# Gadget-Box-PiZero.net
KiCad netlist of a schematic drawn in EAGLE
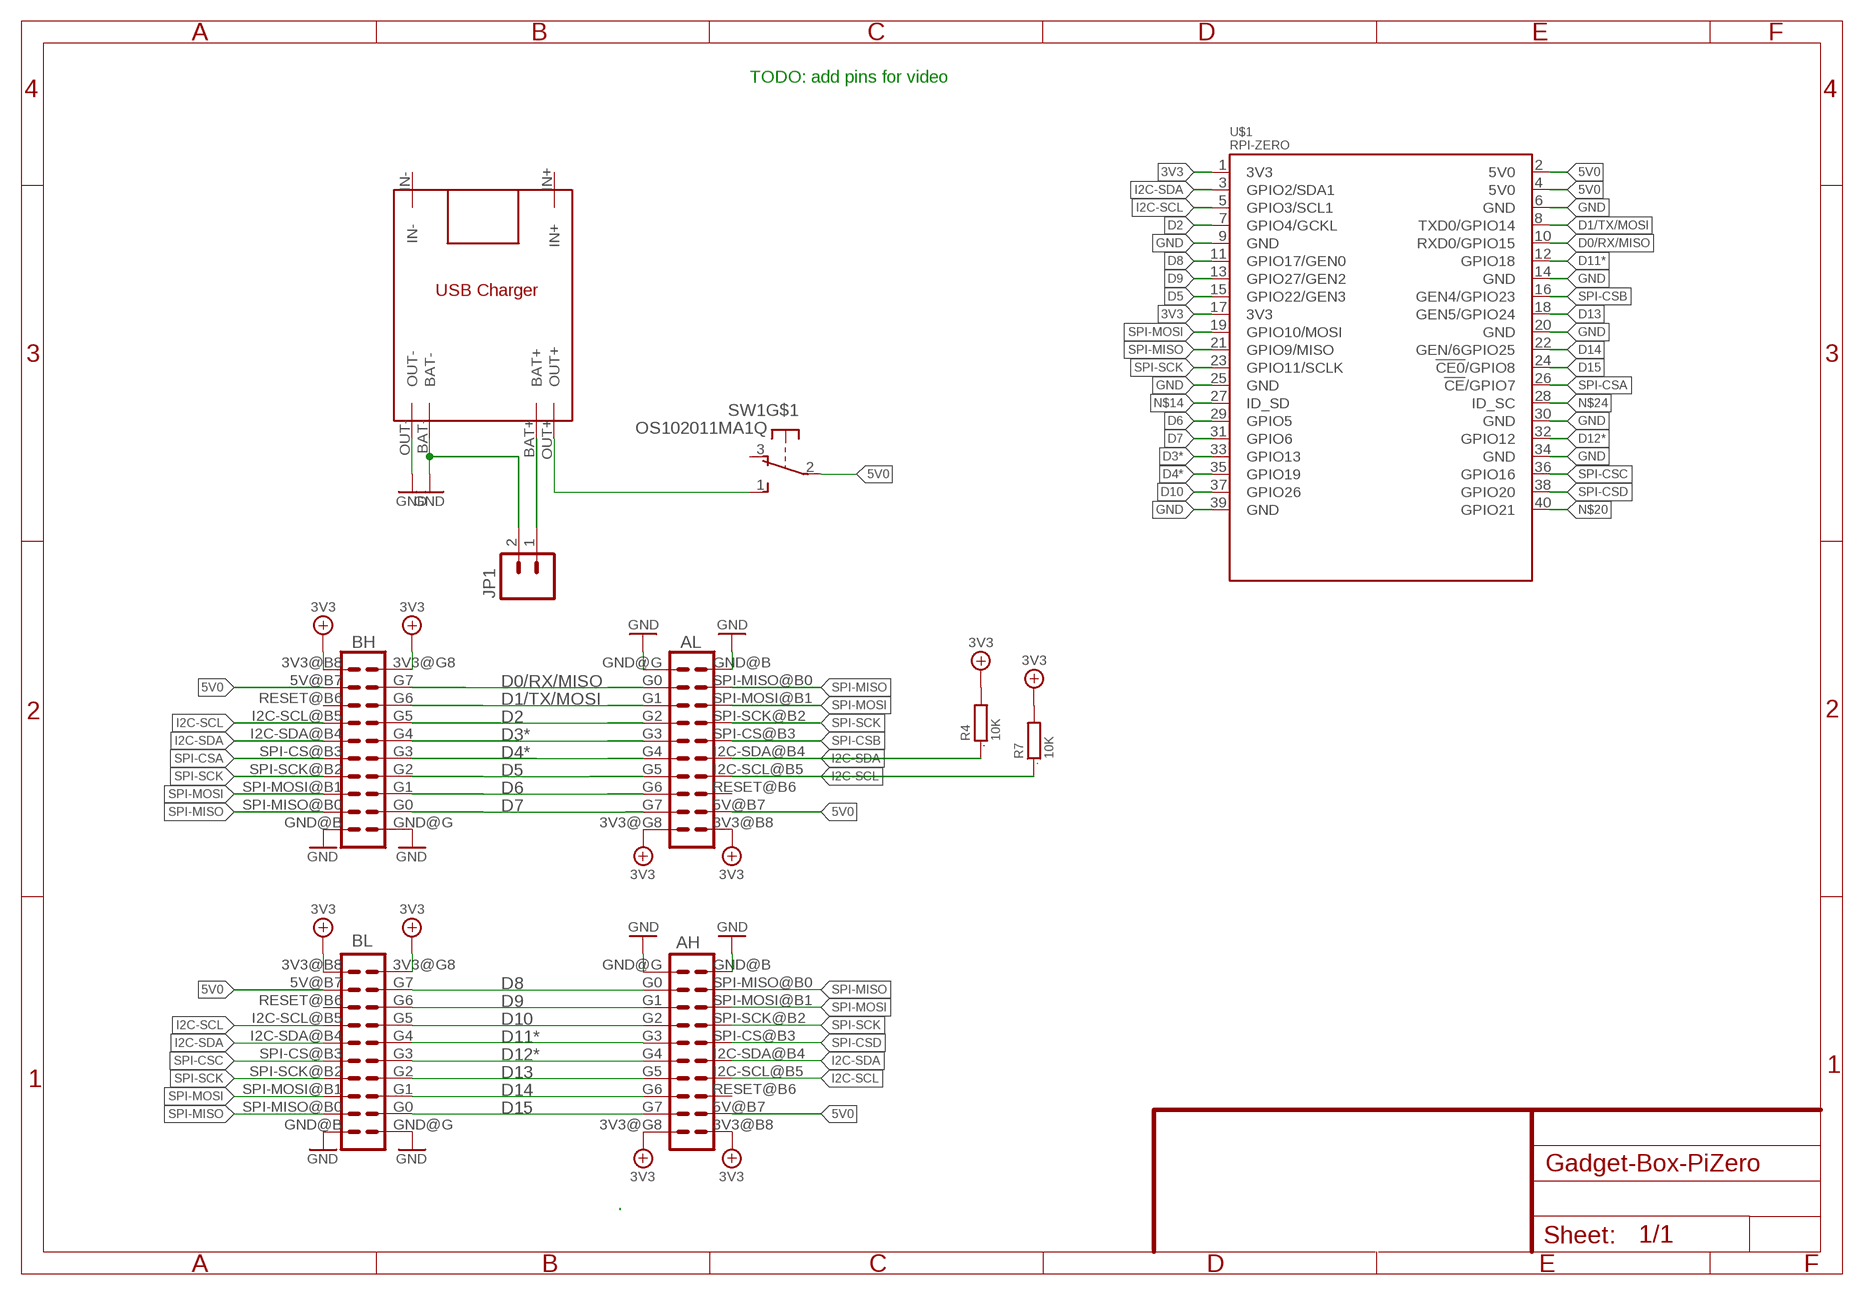
[diagram p0: schematic, sheet 1]

(export (version "E")
  (design (tool "Eeschema 10.0.6"))
  (components
    (comp (ref "AH")
      (value "ECOGECOG_SLOT_ALT1")
      (footprint "eagle-import:ECOG_ALT1")
      (libsource (lib "eagle-import") (part "ECOGECOG_SLOT_ALT1"))
    )
    (comp (ref "AL")
      (value "ECOGECOG_SLOT_ALT1")
      (footprint "eagle-import:ECOG_ALT1")
      (libsource (lib "eagle-import") (part "ECOGECOG_SLOT_ALT1"))
    )
    (comp (ref "BH")
      (value "ECOGECOG_SLOT_ALT1")
      (footprint "eagle-import:ECOG_ALT1")
      (libsource (lib "eagle-import") (part "ECOGECOG_SLOT_ALT1"))
    )
    (comp (ref "BL")
      (value "ECOGECOG_SLOT_ALT1")
      (footprint "eagle-import:ECOG_ALT1")
      (libsource (lib "eagle-import") (part "ECOGECOG_SLOT_ALT1"))
    )
    (comp (ref "JP1")
      (value "M02-JST-2-PTH-NO_SILK")
      (footprint "eagle-import:JST-2-PTH-NS")
      (libsource (lib "eagle-import") (part "M02-JST-2-PTH-NO_SILK"))
    )
    (comp (ref "R4")
      (value "10K")
      (footprint "eagle-import:0603")
      (fields
        (field (name "PARTNO") "RC0603JR-0710KL,YAGEO (VA),dk,311-10KGRCT-ND,RES SMD 10K OHM 5% 1/10W 0603 , REF36")
      )
      (libsource (lib "eagle-import") (part "R0603"))
    )
    (comp (ref "R7")
      (value "10K")
      (footprint "eagle-import:0603")
      (fields
        (field (name "PARTNO") "RC0603JR-0710KL,YAGEO (VA),dk,311-10KGRCT-ND,RES SMD 10K OHM 5% 1/10W 0603 , REF36")
      )
      (libsource (lib "eagle-import") (part "R0603"))
    )
    (comp (ref "SW1")
      (value "OS102011MA1Q")
      (footprint "eagle-import:OS102011MA1Q")
      (libsource (lib "eagle-import") (part "OS102011MA1Q"))
    )
    (comp (ref "U$1")
      (value "RPI-ZERO")
      (footprint "eagle-import:RASPBERRYPI_BASTELSTUBE_V13_RASPI_BOARD_B+_FULL")
      (libsource (lib "eagle-import") (part "RPI-ZERO"))
    )
    (comp (ref "U$2")
      (value "TP4056")
      (footprint "eagle-import:TP4056")
      (libsource (lib "eagle-import") (part "TP4056"))
    )
  )
  (nets
    (net (code "1") (name "3V3") (class "Default")
      (node (ref "AH") (pin "3V3@B8") (pinfunction "3V3_3V3@B8") (pintype "passive"))
      (node (ref "AH") (pin "3V3@G8") (pinfunction "3V3_3V3@G8") (pintype "passive"))
      (node (ref "AL") (pin "3V3@B8") (pinfunction "3V3_3V3@B8") (pintype "passive"))
      (node (ref "AL") (pin "3V3@G8") (pinfunction "3V3_3V3@G8") (pintype "passive"))
      (node (ref "BH") (pin "3V3@B8") (pinfunction "3V3_3V3@B8") (pintype "passive"))
      (node (ref "BH") (pin "3V3@G8") (pinfunction "3V3_3V3@G8") (pintype "passive"))
      (node (ref "BL") (pin "3V3@B8") (pinfunction "3V3_3V3@B8") (pintype "passive"))
      (node (ref "BL") (pin "3V3@G8") (pinfunction "3V3_3V3@G8") (pintype "passive"))
      (node (ref "R4") (pin "2") (pinfunction "2_2") (pintype "passive"))
      (node (ref "R7") (pin "2") (pinfunction "2_2") (pintype "passive"))
      (node (ref "U$1") (pin "1") (pinfunction "3V3_1") (pintype "power_in"))
      (node (ref "U$1") (pin "17") (pinfunction "3V3_17") (pintype "power_in"))
    )
    (net (code "2") (name "5V0") (class "Default")
      (node (ref "AH") (pin "5V@B7") (pinfunction "5V_5V@B7") (pintype "passive"))
      (node (ref "AL") (pin "5V@B7") (pinfunction "5V_5V@B7") (pintype "passive"))
      (node (ref "BH") (pin "5V@B7") (pinfunction "5V_5V@B7") (pintype "passive"))
      (node (ref "BL") (pin "5V@B7") (pinfunction "5V_5V@B7") (pintype "passive"))
      (node (ref "SW1") (pin "2") (pinfunction "P_2") (pintype "passive"))
      (node (ref "U$1") (pin "2") (pinfunction "5V0_2") (pintype "power_in"))
      (node (ref "U$1") (pin "4") (pinfunction "5V0_4") (pintype "power_in"))
    )
    (net (code "3") (name "D0{slash}RX{slash}MISO") (class "Default")
      (node (ref "AL") (pin "G0") (pinfunction "G0_G0") (pintype "passive"))
      (node (ref "BH") (pin "G7") (pinfunction "G7_G7") (pintype "passive"))
      (node (ref "U$1") (pin "10") (pinfunction "RXD0/GPIO15_10") (pintype "bidirectional"))
    )
    (net (code "4") (name "D1{slash}TX{slash}MOSI") (class "Default")
      (node (ref "AL") (pin "G1") (pinfunction "G1_G1") (pintype "passive"))
      (node (ref "BH") (pin "G6") (pinfunction "G6_G6") (pintype "passive"))
      (node (ref "U$1") (pin "8") (pinfunction "TXD0/GPIO14_8") (pintype "bidirectional"))
    )
    (net (code "5") (name "D2") (class "Default")
      (node (ref "AL") (pin "G2") (pinfunction "G2_G2") (pintype "passive"))
      (node (ref "BH") (pin "G5") (pinfunction "G5_G5") (pintype "passive"))
      (node (ref "U$1") (pin "7") (pinfunction "GPIO4/GCKL_7") (pintype "bidirectional"))
    )
    (net (code "6") (name "D3*") (class "Default")
      (node (ref "AL") (pin "G3") (pinfunction "G3_G3") (pintype "passive"))
      (node (ref "BH") (pin "G4") (pinfunction "G4_G4") (pintype "passive"))
      (node (ref "U$1") (pin "33") (pinfunction "GPIO13_33") (pintype "bidirectional"))
    )
    (net (code "7") (name "D4*") (class "Default")
      (node (ref "AL") (pin "G4") (pinfunction "G4_G4") (pintype "passive"))
      (node (ref "BH") (pin "G3") (pinfunction "G3_G3") (pintype "passive"))
      (node (ref "U$1") (pin "35") (pinfunction "GPIO19_35") (pintype "bidirectional"))
    )
    (net (code "8") (name "D5") (class "Default")
      (node (ref "AL") (pin "G5") (pinfunction "G5_G5") (pintype "passive"))
      (node (ref "BH") (pin "G2") (pinfunction "G2_G2") (pintype "passive"))
      (node (ref "U$1") (pin "15") (pinfunction "GPIO22/GEN3_15") (pintype "bidirectional"))
    )
    (net (code "9") (name "D6") (class "Default")
      (node (ref "AL") (pin "G6") (pinfunction "G6_G6") (pintype "passive"))
      (node (ref "BH") (pin "G1") (pinfunction "G1_G1") (pintype "passive"))
      (node (ref "U$1") (pin "29") (pinfunction "GPIO5_29") (pintype "bidirectional"))
    )
    (net (code "10") (name "D7") (class "Default")
      (node (ref "AL") (pin "G7") (pinfunction "G7_G7") (pintype "passive"))
      (node (ref "BH") (pin "G0") (pinfunction "G0_G0") (pintype "passive"))
      (node (ref "U$1") (pin "31") (pinfunction "GPIO6_31") (pintype "bidirectional"))
    )
    (net (code "11") (name "D8") (class "Default")
      (node (ref "AH") (pin "G0") (pinfunction "G0_G0") (pintype "passive"))
      (node (ref "BL") (pin "G7") (pinfunction "G7_G7") (pintype "passive"))
      (node (ref "U$1") (pin "11") (pinfunction "GPIO17/GEN0_11") (pintype "bidirectional"))
    )
    (net (code "12") (name "D9") (class "Default")
      (node (ref "AH") (pin "G1") (pinfunction "G1_G1") (pintype "passive"))
      (node (ref "BL") (pin "G6") (pinfunction "G6_G6") (pintype "passive"))
      (node (ref "U$1") (pin "13") (pinfunction "GPIO27/GEN2_13") (pintype "bidirectional"))
    )
    (net (code "13") (name "D10") (class "Default")
      (node (ref "AH") (pin "G2") (pinfunction "G2_G2") (pintype "passive"))
      (node (ref "BL") (pin "G5") (pinfunction "G5_G5") (pintype "passive"))
      (node (ref "U$1") (pin "37") (pinfunction "GPIO26_37") (pintype "bidirectional"))
    )
    (net (code "14") (name "D11*") (class "Default")
      (node (ref "AH") (pin "G3") (pinfunction "G3_G3") (pintype "passive"))
      (node (ref "BL") (pin "G4") (pinfunction "G4_G4") (pintype "passive"))
      (node (ref "U$1") (pin "12") (pinfunction "GPIO18_12") (pintype "bidirectional"))
    )
    (net (code "15") (name "D12*") (class "Default")
      (node (ref "AH") (pin "G4") (pinfunction "G4_G4") (pintype "passive"))
      (node (ref "BL") (pin "G3") (pinfunction "G3_G3") (pintype "passive"))
      (node (ref "U$1") (pin "32") (pinfunction "GPIO12_32") (pintype "bidirectional"))
    )
    (net (code "16") (name "D13") (class "Default")
      (node (ref "AH") (pin "G5") (pinfunction "G5_G5") (pintype "passive"))
      (node (ref "BL") (pin "G2") (pinfunction "G2_G2") (pintype "passive"))
      (node (ref "U$1") (pin "18") (pinfunction "GEN5/GPIO24_18") (pintype "bidirectional"))
    )
    (net (code "17") (name "D14") (class "Default")
      (node (ref "AH") (pin "G6") (pinfunction "G6_G6") (pintype "passive"))
      (node (ref "BL") (pin "G1") (pinfunction "G1_G1") (pintype "passive"))
      (node (ref "U$1") (pin "22") (pinfunction "GEN/6GPIO25_22") (pintype "bidirectional"))
    )
    (net (code "18") (name "D15") (class "Default")
      (node (ref "AH") (pin "G7") (pinfunction "G7_G7") (pintype "passive"))
      (node (ref "BL") (pin "G0") (pinfunction "G0_G0") (pintype "passive"))
      (node (ref "U$1") (pin "24") (pinfunction "~{CE0}/GPIO8_24") (pintype "bidirectional"))
    )
    (net (code "19") (name "GND") (class "Default")
      (node (ref "AH") (pin "GND@B") (pinfunction "GND_GND@B") (pintype "passive"))
      (node (ref "AH") (pin "GND@G") (pinfunction "GND_GND@G") (pintype "passive"))
      (node (ref "AL") (pin "GND@B") (pinfunction "GND_GND@B") (pintype "passive"))
      (node (ref "AL") (pin "GND@G") (pinfunction "GND_GND@G") (pintype "passive"))
      (node (ref "BH") (pin "GND@B") (pinfunction "GND_GND@B") (pintype "passive"))
      (node (ref "BH") (pin "GND@G") (pinfunction "GND_GND@G") (pintype "passive"))
      (node (ref "BL") (pin "GND@B") (pinfunction "GND_GND@B") (pintype "passive"))
      (node (ref "BL") (pin "GND@G") (pinfunction "GND_GND@G") (pintype "passive"))
      (node (ref "JP1") (pin "2") (pinfunction "2_2") (pintype "passive"))
      (node (ref "U$1") (pin "14") (pinfunction "GND_14") (pintype "power_in"))
      (node (ref "U$1") (pin "20") (pinfunction "GND_20") (pintype "power_in"))
      (node (ref "U$1") (pin "25") (pinfunction "GND_25") (pintype "power_in"))
      (node (ref "U$1") (pin "30") (pinfunction "GND_30") (pintype "power_in"))
      (node (ref "U$1") (pin "34") (pinfunction "GND_34") (pintype "power_in"))
      (node (ref "U$1") (pin "39") (pinfunction "GND_39") (pintype "power_in"))
      (node (ref "U$1") (pin "6") (pinfunction "GND_6") (pintype "power_in"))
      (node (ref "U$1") (pin "9") (pinfunction "GND_9") (pintype "power_in"))
      (node (ref "U$2") (pin "BAT-") (pinfunction "BAT-_BAT-") (pintype "bidirectional"))
      (node (ref "U$2") (pin "OUT-") (pinfunction "OUT-_OUT-") (pintype "bidirectional"))
    )
    (net (code "20") (name "I2C-SCL") (class "Default")
      (node (ref "AH") (pin "I2C-SCL@B5") (pinfunction "I2C-SCL_I2C-SCL@B5") (pintype "passive"))
      (node (ref "AL") (pin "I2C-SCL@B5") (pinfunction "I2C-SCL_I2C-SCL@B5") (pintype "passive"))
      (node (ref "BH") (pin "I2C-SCL@B5") (pinfunction "I2C-SCL_I2C-SCL@B5") (pintype "passive"))
      (node (ref "BL") (pin "I2C-SCL@B5") (pinfunction "I2C-SCL_I2C-SCL@B5") (pintype "passive"))
      (node (ref "R7") (pin "1") (pinfunction "1_1") (pintype "passive"))
      (node (ref "U$1") (pin "5") (pinfunction "GPIO3/SCL1_5") (pintype "bidirectional"))
    )
    (net (code "21") (name "I2C-SDA") (class "Default")
      (node (ref "AH") (pin "I2C-SDA@B4") (pinfunction "I2C-SDA_I2C-SDA@B4") (pintype "passive"))
      (node (ref "AL") (pin "I2C-SDA@B4") (pinfunction "I2C-SDA_I2C-SDA@B4") (pintype "passive"))
      (node (ref "BH") (pin "I2C-SDA@B4") (pinfunction "I2C-SDA_I2C-SDA@B4") (pintype "passive"))
      (node (ref "BL") (pin "I2C-SDA@B4") (pinfunction "I2C-SDA_I2C-SDA@B4") (pintype "passive"))
      (node (ref "R4") (pin "1") (pinfunction "1_1") (pintype "passive"))
      (node (ref "U$1") (pin "3") (pinfunction "GPIO2/SDA1_3") (pintype "bidirectional"))
    )
    (net (code "22") (name "N$14") (class "Default")
      (node (ref "U$1") (pin "27") (pinfunction "ID_SD_27") (pintype "bidirectional"))
    )
    (net (code "23") (name "N$20") (class "Default")
      (node (ref "U$1") (pin "40") (pinfunction "GPIO21_40") (pintype "bidirectional"))
    )
    (net (code "24") (name "N$24") (class "Default")
      (node (ref "U$1") (pin "28") (pinfunction "ID_SC_28") (pintype "bidirectional"))
    )
    (net (code "25") (name "Net-(JP1-Pad1)") (class "Default")
      (node (ref "JP1") (pin "1") (pinfunction "1_1") (pintype "passive"))
      (node (ref "U$2") (pin "BAT+") (pinfunction "BAT+_BAT+") (pintype "bidirectional"))
    )
    (net (code "26") (name "Net-(SW1A-S)") (class "Default")
      (node (ref "SW1") (pin "1") (pinfunction "S_1") (pintype "passive"))
      (node (ref "U$2") (pin "OUT+") (pinfunction "OUT+_OUT+") (pintype "bidirectional"))
    )
    (net (code "27") (name "SPI-CSA") (class "Default")
      (node (ref "BH") (pin "SPI-CS@B3") (pinfunction "SPI-CS_SPI-CS@B3") (pintype "passive"))
      (node (ref "U$1") (pin "26") (pinfunction "~{CE}/GPIO7_26") (pintype "bidirectional"))
    )
    (net (code "28") (name "SPI-CSB") (class "Default")
      (node (ref "AL") (pin "SPI-CS@B3") (pinfunction "SPI-CS_SPI-CS@B3") (pintype "passive"))
      (node (ref "U$1") (pin "16") (pinfunction "GEN4/GPIO23_16") (pintype "bidirectional"))
    )
    (net (code "29") (name "SPI-CSC") (class "Default")
      (node (ref "BL") (pin "SPI-CS@B3") (pinfunction "SPI-CS_SPI-CS@B3") (pintype "passive"))
      (node (ref "U$1") (pin "36") (pinfunction "GPIO16_36") (pintype "bidirectional"))
    )
    (net (code "30") (name "SPI-CSD") (class "Default")
      (node (ref "AH") (pin "SPI-CS@B3") (pinfunction "SPI-CS_SPI-CS@B3") (pintype "passive"))
      (node (ref "U$1") (pin "38") (pinfunction "GPIO20_38") (pintype "bidirectional"))
    )
    (net (code "31") (name "SPI-MISO") (class "Default")
      (node (ref "AH") (pin "SPI-MISO@B0") (pinfunction "SPI-MISO_SPI-MISO@B0") (pintype "passive"))
      (node (ref "AL") (pin "SPI-MISO@B0") (pinfunction "SPI-MISO_SPI-MISO@B0") (pintype "passive"))
      (node (ref "BH") (pin "SPI-MISO@B0") (pinfunction "SPI-MISO_SPI-MISO@B0") (pintype "passive"))
      (node (ref "BL") (pin "SPI-MISO@B0") (pinfunction "SPI-MISO_SPI-MISO@B0") (pintype "passive"))
      (node (ref "U$1") (pin "21") (pinfunction "GPIO9/MISO_21") (pintype "bidirectional"))
    )
    (net (code "32") (name "SPI-MOSI") (class "Default")
      (node (ref "AH") (pin "SPI-MOSI@B1") (pinfunction "SPI-MOSI_SPI-MOSI@B1") (pintype "passive"))
      (node (ref "AL") (pin "SPI-MOSI@B1") (pinfunction "SPI-MOSI_SPI-MOSI@B1") (pintype "passive"))
      (node (ref "BH") (pin "SPI-MOSI@B1") (pinfunction "SPI-MOSI_SPI-MOSI@B1") (pintype "passive"))
      (node (ref "BL") (pin "SPI-MOSI@B1") (pinfunction "SPI-MOSI_SPI-MOSI@B1") (pintype "passive"))
      (node (ref "U$1") (pin "19") (pinfunction "GPIO10/MOSI_19") (pintype "bidirectional"))
    )
    (net (code "33") (name "SPI-SCK") (class "Default")
      (node (ref "AH") (pin "SPI-SCK@B2") (pinfunction "SPI-SCK_SPI-SCK@B2") (pintype "passive"))
      (node (ref "AL") (pin "SPI-SCK@B2") (pinfunction "SPI-SCK_SPI-SCK@B2") (pintype "passive"))
      (node (ref "BH") (pin "SPI-SCK@B2") (pinfunction "SPI-SCK_SPI-SCK@B2") (pintype "passive"))
      (node (ref "BL") (pin "SPI-SCK@B2") (pinfunction "SPI-SCK_SPI-SCK@B2") (pintype "passive"))
      (node (ref "U$1") (pin "23") (pinfunction "GPIO11/SCLK_23") (pintype "bidirectional"))
    )
    (net (code "34") (name "unconnected-(AH-RESET-PadRESET@B6)") (class "Default")
      (node (ref "AH") (pin "RESET@B6") (pinfunction "RESET_RESET@B6") (pintype "passive"))
    )
    (net (code "35") (name "unconnected-(AL-RESET-PadRESET@B6)") (class "Default")
      (node (ref "AL") (pin "RESET@B6") (pinfunction "RESET_RESET@B6") (pintype "passive"))
    )
    (net (code "36") (name "unconnected-(BH-RESET-PadRESET@B6)") (class "Default")
      (node (ref "BH") (pin "RESET@B6") (pinfunction "RESET_RESET@B6") (pintype "passive"))
    )
    (net (code "37") (name "unconnected-(BL-RESET-PadRESET@B6)") (class "Default")
      (node (ref "BL") (pin "RESET@B6") (pinfunction "RESET_RESET@B6") (pintype "passive"))
    )
    (net (code "38") (name "unconnected-(SW1A-O-Pad3)") (class "Default")
      (node (ref "SW1") (pin "3") (pinfunction "O_3") (pintype "passive"))
    )
    (net (code "39") (name "unconnected-(U$2-PadIN+)") (class "Default")
      (node (ref "U$2") (pin "IN+") (pinfunction "IN+_IN+") (pintype "bidirectional"))
    )
    (net (code "40") (name "unconnected-(U$2-PadIN-)") (class "Default")
      (node (ref "U$2") (pin "IN-") (pinfunction "IN-_IN-") (pintype "bidirectional"))
    )
  )
)
